# EE209_Schematic.net
KiCad netlist of a schematic drawn in Altium Designer
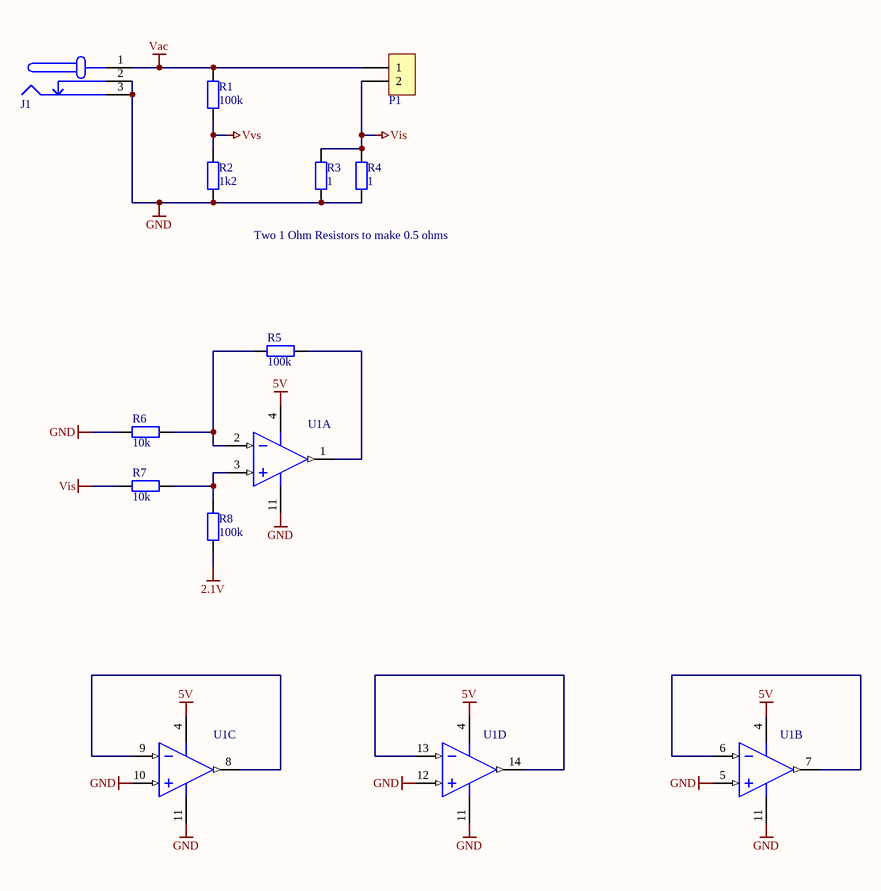
[diagram p0: EE209_Schematic.SchDoc]

(export (version "E")
  (design (tool "Eeschema 10.0.6"))
  (components
    (comp (ref "J1")
      (value "DC barrel jack")
      (footprint "AC-Socket")
      (description "DC barrel jack connection to AC source")
      (libsource (lib "EE209_Library") (part "AC_Input"))
    )
    (comp (ref "P1")
      (value "Dual Banana Plugs")
      (footprint "Dual Banana Plug")
      (description "Dual banana plugs connection to the AC load")
      (fields (field (name "PUBLISHER") "Altium Limited"))
      (libsource (lib "EE209_Library") (part "AC_Output"))
    )
    (comp (ref "R1")
      (value "100k")
      (footprint "AXIAL-0.4")
      (description "Through hole resistor")
      (fields (field (name "PUBLISHER") "Altium Limited"))
      (libsource (lib "EE209_Library") (part "Res_TH_0AX4"))
    )
    (comp (ref "R2")
      (value "1k2")
      (footprint "AXIAL-0.4")
      (description "Through hole resistor")
      (fields (field (name "PUBLISHER") "Altium Limited"))
      (libsource (lib "EE209_Library") (part "Res_TH_0AX4"))
    )
    (comp (ref "R3")
      (value "1")
      (footprint "AXIAL-0.4")
      (description "Through hole resistor")
      (fields (field (name "PUBLISHER") "Altium Limited"))
      (libsource (lib "EE209_Library") (part "Res_TH_0AX4"))
    )
    (comp (ref "R4")
      (value "1")
      (footprint "AXIAL-0.4")
      (description "Through hole resistor")
      (fields (field (name "PUBLISHER") "Altium Limited"))
      (libsource (lib "EE209_Library") (part "Res_TH_0AX4"))
    )
    (comp (ref "R5")
      (value "100k")
      (footprint "AXIAL-0.4")
      (description "Through hole resistor")
      (fields (field (name "PUBLISHER") "Altium Limited"))
      (libsource (lib "") (part "Res_TH_0AX4_1"))
    )
    (comp (ref "R6")
      (value "10k")
      (footprint "AXIAL-0.4")
      (description "Through hole resistor")
      (fields (field (name "PUBLISHER") "Altium Limited"))
      (libsource (lib "") (part "Res_TH_0AX4_1"))
    )
    (comp (ref "R7")
      (value "10k")
      (footprint "AXIAL-0.4")
      (description "Through hole resistor")
      (fields (field (name "PUBLISHER") "Altium Limited"))
      (libsource (lib "") (part "Res_TH_0AX4_1"))
    )
    (comp (ref "R8")
      (value "100k")
      (footprint "AXIAL-0.4")
      (description "Through hole resistor")
      (fields (field (name "PUBLISHER") "Altium Limited"))
      (libsource (lib "EE209_Library") (part "Res_TH_0AX4"))
    )
    (comp (ref "U1")
      (value "LM324")
      (footprint "DIP-14")
      (description "IC OPAMP GP 14DIP")
      (fields
        (field (name "MANUFACTURER") "ON Semiconductor")
        (field (name "MANUFACTURER PART NUMBER") "LM324N")
      )
      (libsource (lib "EE209_Library") (part "LM324N_TH_DIP16"))
    )
  )
  (nets
    (net (code "1") (name "2.1V") (class "Default")
      (node (ref "R8") (pin "1") (pinfunction "1_1") (pintype "passive"))
    )
    (net (code "2") (name "5V") (class "Default")
      (node (ref "U1") (pin "4") (pinfunction "VDD_4") (pintype "power_in"))
    )
    (net (code "3") (name "GND") (class "Default")
      (node (ref "J1") (pin "2") (pinfunction "GND_ALT_2") (pintype "power_in"))
      (node (ref "J1") (pin "3") (pinfunction "GND_3") (pintype "power_in"))
      (node (ref "R2") (pin "1") (pinfunction "1_1") (pintype "passive"))
      (node (ref "R3") (pin "1") (pinfunction "1_1") (pintype "passive"))
      (node (ref "R4") (pin "1") (pinfunction "1_1") (pintype "passive"))
      (node (ref "R6") (pin "1") (pinfunction "1_1") (pintype "passive"))
      (node (ref "U1") (pin "10") (pinfunction "VINC+_10") (pintype "input"))
      (node (ref "U1") (pin "11") (pinfunction "VSS_11") (pintype "power_in"))
      (node (ref "U1") (pin "12") (pinfunction "VIND+_12") (pintype "input"))
      (node (ref "U1") (pin "5") (pinfunction "VINB+_5") (pintype "input"))
    )
    (net (code "4") (name "Net-(U1A-VINA+)") (class "Default")
      (node (ref "R7") (pin "2") (pinfunction "2_2") (pintype "passive"))
      (node (ref "R8") (pin "2") (pinfunction "2_2") (pintype "passive"))
      (node (ref "U1") (pin "3") (pinfunction "VINA+_3") (pintype "input"))
    )
    (net (code "5") (name "Net-(U1A-VINA-)") (class "Default")
      (node (ref "R5") (pin "1") (pinfunction "1_1") (pintype "passive"))
      (node (ref "R6") (pin "2") (pinfunction "2_2") (pintype "passive"))
      (node (ref "U1") (pin "2") (pinfunction "VINA-_2") (pintype "input"))
    )
    (net (code "6") (name "Net-(U1A-VOUTA)") (class "Default")
      (node (ref "R5") (pin "2") (pinfunction "2_2") (pintype "passive"))
      (node (ref "U1") (pin "1") (pinfunction "VOUTA_1") (pintype "output"))
    )
    (net (code "7") (name "Net-(U1B-VINB-)") (class "Default")
      (node (ref "U1") (pin "6") (pinfunction "VINB-_6") (pintype "input"))
      (node (ref "U1") (pin "7") (pinfunction "VOUTB_7") (pintype "output"))
    )
    (net (code "8") (name "Net-(U1C-VINC-)") (class "Default")
      (node (ref "U1") (pin "8") (pinfunction "VOUTC_8") (pintype "output"))
      (node (ref "U1") (pin "9") (pinfunction "VINC-_9") (pintype "input"))
    )
    (net (code "9") (name "Net-(U1D-VIND-)") (class "Default")
      (node (ref "U1") (pin "13") (pinfunction "VIND-_13") (pintype "input"))
      (node (ref "U1") (pin "14") (pinfunction "VOUTD_14") (pintype "output"))
    )
    (net (code "10") (name "Vac") (class "Default")
      (node (ref "J1") (pin "1") (pinfunction "VCC_1") (pintype "power_in"))
      (node (ref "P1") (pin "1") (pinfunction "1_1") (pintype "passive"))
      (node (ref "R1") (pin "2") (pinfunction "2_2") (pintype "passive"))
    )
    (net (code "11") (name "Vis") (class "Default")
      (node (ref "P1") (pin "2") (pinfunction "2_2") (pintype "passive"))
      (node (ref "R3") (pin "2") (pinfunction "2_2") (pintype "passive"))
      (node (ref "R4") (pin "2") (pinfunction "2_2") (pintype "passive"))
      (node (ref "R7") (pin "1") (pinfunction "1_1") (pintype "passive"))
    )
    (net (code "12") (name "Vvs") (class "Default")
      (node (ref "R1") (pin "1") (pinfunction "1_1") (pintype "passive"))
      (node (ref "R2") (pin "2") (pinfunction "2_2") (pintype "passive"))
    )
  )
)
